# 13_GPIO.net
KiCad netlist of a schematic drawn in Altium Designer
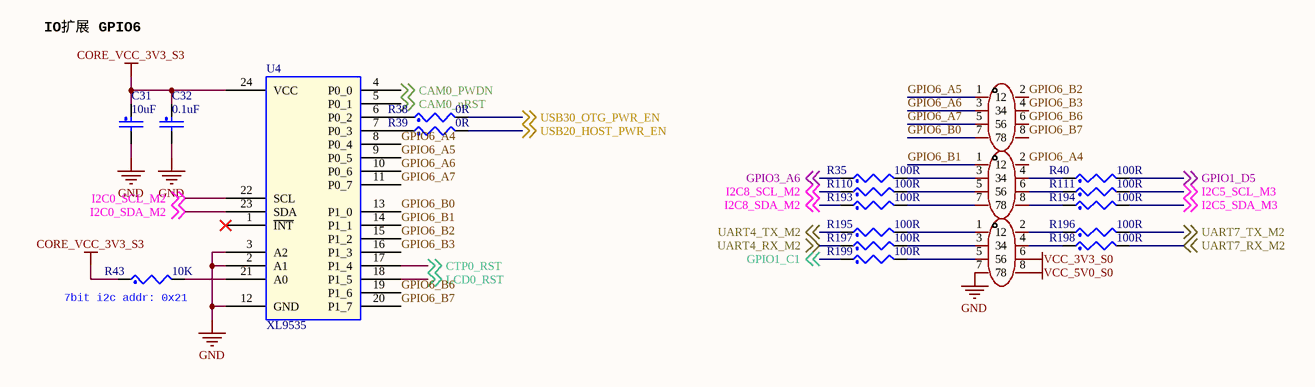
[diagram p0: 13.GPIO扩展接口.SchDoc]

(export (version "E")
  (design (tool "Eeschema 10.0.6"))
  (components
    (comp (ref "C31") (value "10uF") (footprint "0.PCB1:C0402") (libsource (lib "RK3588底板") (part "CAP_NP")))
    (comp (ref "C32") (value "0.1uF") (footprint "0.PCB1:C0402") (libsource (lib "RK3588底板") (part "CAP_NP")))
    (comp (ref "H1")
      (value "HX PZ2.0-2x4P WT")
      (footprint "0.PCB1:HDR-SMD_HX-PZ2.0-2X4P-WT")
      (libsource (lib "RK3588底板") (part "HX PZ2.0-2x4P WT"))
    )
    (comp (ref "H2")
      (value "HX PZ2.0-2x4P WT")
      (footprint "0.PCB1:HDR-SMD_HX-PZ2.0-2X4P-WT")
      (libsource (lib "RK3588底板") (part "HX PZ2.0-2x4P WT"))
    )
    (comp (ref "H3")
      (value "HX PZ2.0-2x4P WT")
      (footprint "0.PCB1:HDR-SMD_HX-PZ2.0-2X4P-WT")
      (libsource (lib "RK3588底板") (part "HX PZ2.0-2x4P WT"))
    )
    (comp (ref "R35") (value "100R") (footprint "0.PCB1:R0402") (libsource (lib "RK3588底板") (part "RES")))
    (comp (ref "R38") (value "0R") (footprint "0.PCB1:R0402") (libsource (lib "RK3588底板") (part "RES")))
    (comp (ref "R39") (value "0R") (footprint "0.PCB1:R0402") (libsource (lib "RK3588底板") (part "RES")))
    (comp (ref "R40") (value "100R") (footprint "0.PCB1:R0402") (libsource (lib "RK3588底板") (part "RES")))
    (comp (ref "R43") (value "10K") (footprint "0.PCB1:R0402") (libsource (lib "RK3588底板") (part "RES")))
    (comp (ref "R110") (value "100R") (footprint "0.PCB1:R0402") (libsource (lib "RK3588底板") (part "RES")))
    (comp (ref "R111") (value "100R") (footprint "0.PCB1:R0402") (libsource (lib "RK3588底板") (part "RES")))
    (comp (ref "R193") (value "100R") (footprint "0.PCB1:R0402") (libsource (lib "RK3588底板") (part "RES")))
    (comp (ref "R194") (value "100R") (footprint "0.PCB1:R0402") (libsource (lib "RK3588底板") (part "RES")))
    (comp (ref "R195") (value "100R") (footprint "0.PCB1:R0402") (libsource (lib "RK3588底板") (part "RES")))
    (comp (ref "R196") (value "100R") (footprint "0.PCB1:R0402") (libsource (lib "RK3588底板") (part "RES")))
    (comp (ref "R197") (value "100R") (footprint "0.PCB1:R0402") (libsource (lib "RK3588底板") (part "RES")))
    (comp (ref "R198") (value "100R") (footprint "0.PCB1:R0402") (libsource (lib "RK3588底板") (part "RES")))
    (comp (ref "R199") (value "100R") (footprint "0.PCB1:R0402") (libsource (lib "RK3588底板") (part "RES")))
    (comp (ref "U4")
      (value "XL9535")
      (footprint "0.PCB1:TSSOP24-0R65-7R80X4R40")
      (libsource (lib "RK3588底板") (part "XL9535"))
    )
  )
  (nets
    (net (code "1") (name "/GPIO6_A4") (class "Default")
      (node (ref "H2") (pin "2") (pinfunction "2_2") (pintype "passive"))
      (node (ref "U4") (pin "8") (pinfunction "P0_4_8") (pintype "passive"))
    )
    (net (code "2") (name "/GPIO6_A5") (class "Default")
      (node (ref "H1") (pin "1") (pinfunction "1_1") (pintype "passive"))
      (node (ref "U4") (pin "9") (pinfunction "P0_5_9") (pintype "passive"))
    )
    (net (code "3") (name "/GPIO6_A6") (class "Default")
      (node (ref "H1") (pin "3") (pinfunction "3_3") (pintype "passive"))
      (node (ref "U4") (pin "10") (pinfunction "P0_6_10") (pintype "passive"))
    )
    (net (code "4") (name "/GPIO6_A7") (class "Default")
      (node (ref "H1") (pin "5") (pinfunction "5_5") (pintype "passive"))
      (node (ref "U4") (pin "11") (pinfunction "P0_7_11") (pintype "passive"))
    )
    (net (code "5") (name "/GPIO6_B0") (class "Default")
      (node (ref "H1") (pin "7") (pinfunction "7_7") (pintype "passive"))
      (node (ref "U4") (pin "13") (pinfunction "P1_0_13") (pintype "passive"))
    )
    (net (code "6") (name "/GPIO6_B1") (class "Default")
      (node (ref "H2") (pin "1") (pinfunction "1_1") (pintype "passive"))
      (node (ref "U4") (pin "14") (pinfunction "P1_1_14") (pintype "passive"))
    )
    (net (code "7") (name "/GPIO6_B2") (class "Default")
      (node (ref "H1") (pin "2") (pinfunction "2_2") (pintype "passive"))
      (node (ref "U4") (pin "15") (pinfunction "P1_2_15") (pintype "passive"))
    )
    (net (code "8") (name "/GPIO6_B3") (class "Default")
      (node (ref "H1") (pin "4") (pinfunction "4_4") (pintype "passive"))
      (node (ref "U4") (pin "16") (pinfunction "P1_3_16") (pintype "passive"))
    )
    (net (code "9") (name "/GPIO6_B6") (class "Default")
      (node (ref "H1") (pin "6") (pinfunction "6_6") (pintype "passive"))
      (node (ref "U4") (pin "19") (pinfunction "P1_6_19") (pintype "passive"))
    )
    (net (code "10") (name "/GPIO6_B7") (class "Default")
      (node (ref "H1") (pin "8") (pinfunction "8_8") (pintype "passive"))
      (node (ref "U4") (pin "20") (pinfunction "P1_7_20") (pintype "passive"))
    )
    (net (code "11") (name "CAM0_PWDN") (class "Default")
      (node (ref "U4") (pin "4") (pinfunction "P0_0_4") (pintype "passive"))
    )
    (net (code "12") (name "CAM0_nRST") (class "Default")
      (node (ref "U4") (pin "5") (pinfunction "P0_1_5") (pintype "passive"))
    )
    (net (code "13") (name "CORE_VCC_3V3_S3") (class "Default")
      (node (ref "C31") (pin "1") (pinfunction "1_1") (pintype "passive"))
      (node (ref "C32") (pin "1") (pinfunction "1_1") (pintype "passive"))
      (node (ref "R43") (pin "1") (pinfunction "1_1") (pintype "passive"))
      (node (ref "U4") (pin "24") (pinfunction "VCC_24") (pintype "passive"))
    )
    (net (code "14") (name "CTP0_RST") (class "Default")
      (node (ref "U4") (pin "17") (pinfunction "P1_4_17") (pintype "passive"))
    )
    (net (code "15") (name "GND") (class "Default")
      (node (ref "C31") (pin "2") (pinfunction "2_2") (pintype "passive"))
      (node (ref "C32") (pin "2") (pinfunction "2_2") (pintype "passive"))
      (node (ref "H3") (pin "7") (pinfunction "7_7") (pintype "passive"))
      (node (ref "U4") (pin "12") (pinfunction "GND_12") (pintype "passive"))
      (node (ref "U4") (pin "2") (pinfunction "A1_2") (pintype "passive"))
      (node (ref "U4") (pin "3") (pinfunction "A2_3") (pintype "passive"))
    )
    (net (code "16") (name "GPIO1_C1") (class "Default")
      (node (ref "R199") (pin "1") (pinfunction "1_1") (pintype "passive"))
    )
    (net (code "17") (name "GPIO1_D5") (class "Default")
      (node (ref "R40") (pin "2") (pinfunction "2_2") (pintype "passive"))
    )
    (net (code "18") (name "GPIO3_A6") (class "Default")
      (node (ref "R35") (pin "1") (pinfunction "1_1") (pintype "passive"))
    )
    (net (code "19") (name "I2C0_SCL_M2") (class "Default")
      (node (ref "U4") (pin "22") (pinfunction "SCL_22") (pintype "passive"))
    )
    (net (code "20") (name "I2C0_SDA_M2") (class "Default")
      (node (ref "U4") (pin "23") (pinfunction "SDA_23") (pintype "passive"))
    )
    (net (code "21") (name "I2C5_SCL_M3") (class "Default")
      (node (ref "R111") (pin "2") (pinfunction "2_2") (pintype "passive"))
    )
    (net (code "22") (name "I2C5_SDA_M3") (class "Default")
      (node (ref "R194") (pin "2") (pinfunction "2_2") (pintype "passive"))
    )
    (net (code "23") (name "I2C8_SCL_M2") (class "Default")
      (node (ref "R110") (pin "1") (pinfunction "1_1") (pintype "passive"))
    )
    (net (code "24") (name "I2C8_SDA_M2") (class "Default")
      (node (ref "R193") (pin "1") (pinfunction "1_1") (pintype "passive"))
    )
    (net (code "25") (name "LCD0_RST") (class "Default")
      (node (ref "U4") (pin "18") (pinfunction "P1_5_18") (pintype "passive"))
    )
    (net (code "26") (name "Net-(H2-Pad3)") (class "Default")
      (node (ref "H2") (pin "3") (pinfunction "3_3") (pintype "passive"))
      (node (ref "R35") (pin "2") (pinfunction "2_2") (pintype "passive"))
    )
    (net (code "27") (name "Net-(H2-Pad4)") (class "Default")
      (node (ref "H2") (pin "4") (pinfunction "4_4") (pintype "passive"))
      (node (ref "R40") (pin "1") (pinfunction "1_1") (pintype "passive"))
    )
    (net (code "28") (name "Net-(H2-Pad5)") (class "Default")
      (node (ref "H2") (pin "5") (pinfunction "5_5") (pintype "passive"))
      (node (ref "R110") (pin "2") (pinfunction "2_2") (pintype "passive"))
    )
    (net (code "29") (name "Net-(H2-Pad6)") (class "Default")
      (node (ref "H2") (pin "6") (pinfunction "6_6") (pintype "passive"))
      (node (ref "R111") (pin "1") (pinfunction "1_1") (pintype "passive"))
    )
    (net (code "30") (name "Net-(H2-Pad7)") (class "Default")
      (node (ref "H2") (pin "7") (pinfunction "7_7") (pintype "passive"))
      (node (ref "R193") (pin "2") (pinfunction "2_2") (pintype "passive"))
    )
    (net (code "31") (name "Net-(H2-Pad8)") (class "Default")
      (node (ref "H2") (pin "8") (pinfunction "8_8") (pintype "passive"))
      (node (ref "R194") (pin "1") (pinfunction "1_1") (pintype "passive"))
    )
    (net (code "32") (name "Net-(H3-Pad1)") (class "Default")
      (node (ref "H3") (pin "1") (pinfunction "1_1") (pintype "passive"))
      (node (ref "R195") (pin "2") (pinfunction "2_2") (pintype "passive"))
    )
    (net (code "33") (name "Net-(H3-Pad2)") (class "Default")
      (node (ref "H3") (pin "2") (pinfunction "2_2") (pintype "passive"))
      (node (ref "R196") (pin "1") (pinfunction "1_1") (pintype "passive"))
    )
    (net (code "34") (name "Net-(H3-Pad3)") (class "Default")
      (node (ref "H3") (pin "3") (pinfunction "3_3") (pintype "passive"))
      (node (ref "R197") (pin "2") (pinfunction "2_2") (pintype "passive"))
    )
    (net (code "35") (name "Net-(H3-Pad4)") (class "Default")
      (node (ref "H3") (pin "4") (pinfunction "4_4") (pintype "passive"))
      (node (ref "R198") (pin "1") (pinfunction "1_1") (pintype "passive"))
    )
    (net (code "36") (name "Net-(H3-Pad5)") (class "Default")
      (node (ref "H3") (pin "5") (pinfunction "5_5") (pintype "passive"))
      (node (ref "R199") (pin "2") (pinfunction "2_2") (pintype "passive"))
    )
    (net (code "37") (name "Net-(U4-A0)") (class "Default")
      (node (ref "R43") (pin "2") (pinfunction "2_2") (pintype "passive"))
      (node (ref "U4") (pin "21") (pinfunction "A0_21") (pintype "passive"))
    )
    (net (code "38") (name "Net-(U4-P0_2)") (class "Default")
      (node (ref "R38") (pin "1") (pinfunction "1_1") (pintype "passive"))
      (node (ref "U4") (pin "6") (pinfunction "P0_2_6") (pintype "passive"))
    )
    (net (code "39") (name "Net-(U4-P0_3)") (class "Default")
      (node (ref "R39") (pin "1") (pinfunction "1_1") (pintype "passive"))
      (node (ref "U4") (pin "7") (pinfunction "P0_3_7") (pintype "passive"))
    )
    (net (code "40") (name "UART4_RX_M2") (class "Default")
      (node (ref "R197") (pin "1") (pinfunction "1_1") (pintype "passive"))
    )
    (net (code "41") (name "UART4_TX_M2") (class "Default")
      (node (ref "R195") (pin "1") (pinfunction "1_1") (pintype "passive"))
    )
    (net (code "42") (name "UART7_RX_M2") (class "Default")
      (node (ref "R198") (pin "2") (pinfunction "2_2") (pintype "passive"))
    )
    (net (code "43") (name "UART7_TX_M2") (class "Default")
      (node (ref "R196") (pin "2") (pinfunction "2_2") (pintype "passive"))
    )
    (net (code "44") (name "USB20_HOST_PWR_EN") (class "Default")
      (node (ref "R39") (pin "2") (pinfunction "2_2") (pintype "passive"))
    )
    (net (code "45") (name "USB30_OTG_PWR_EN") (class "Default")
      (node (ref "R38") (pin "2") (pinfunction "2_2") (pintype "passive"))
    )
    (net (code "46") (name "VCC_3V3_S0") (class "Default")
      (node (ref "H3") (pin "6") (pinfunction "6_6") (pintype "passive"))
    )
    (net (code "47") (name "VCC_5V0_S0") (class "Default")
      (node (ref "H3") (pin "8") (pinfunction "8_8") (pintype "passive"))
    )
    (net (code "48") (name "unconnected-(U4-~{INT}-Pad1)") (class "Default")
      (node (ref "U4") (pin "1") (pinfunction "~{INT}_1") (pintype "passive+no_connect"))
    )
  )
)
